# RGB_Ring_SCH.net
KiCad netlist of a schematic drawn in Altium Designer
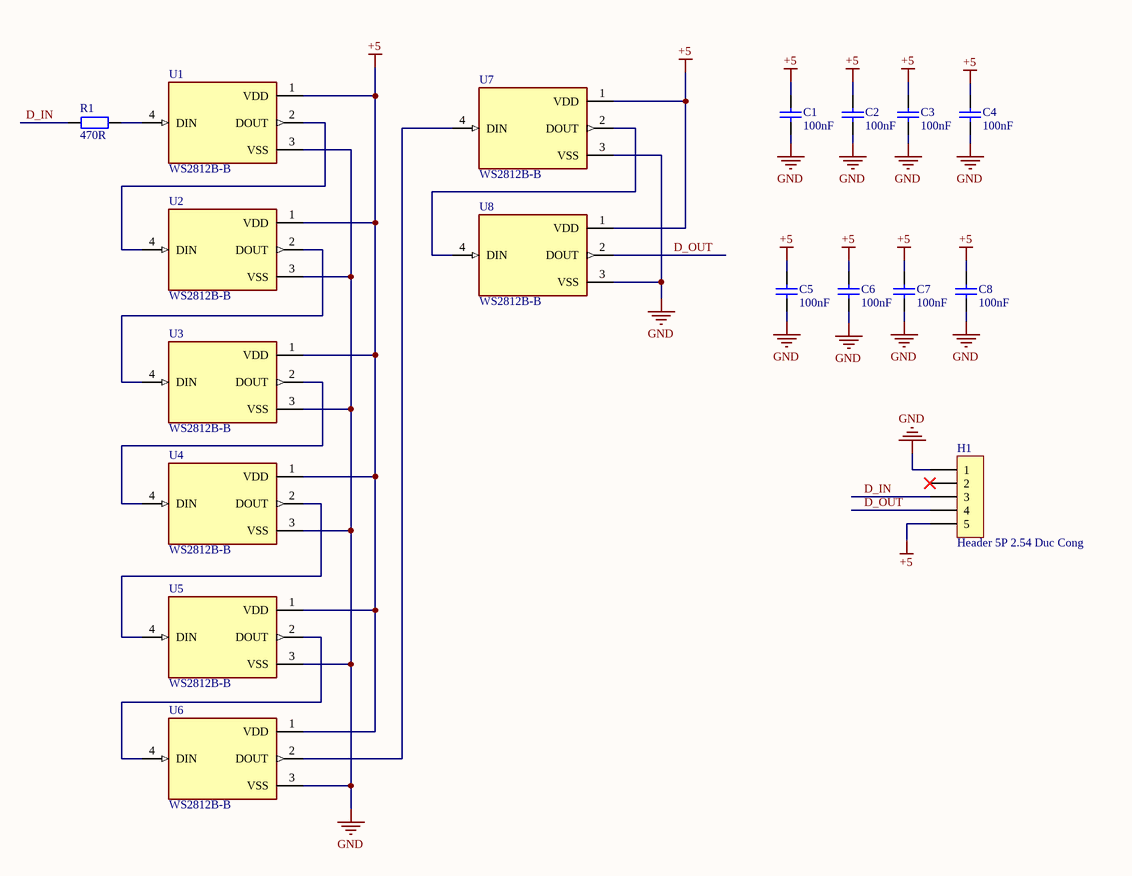
[diagram p0: RGB_Ring_SCH.SchDoc]

(export (version "E")
  (design (tool "Eeschema 10.0.6"))
  (components
    (comp (ref "C1")
      (value "100nF")
      (footprint "tu 0603")
      (description "Dán")
      (libsource (lib "namnt_Lib") (part "Tu 0603 104 50V 10%"))
    )
    (comp (ref "C2")
      (value "100nF")
      (footprint "tu 0603")
      (description "Dán")
      (libsource (lib "namnt_Lib") (part "Tu 0603 104 50V 10%"))
    )
    (comp (ref "C3")
      (value "100nF")
      (footprint "tu 0603")
      (description "Dán")
      (libsource (lib "namnt_Lib") (part "Tu 0603 104 50V 10%"))
    )
    (comp (ref "C4")
      (value "100nF")
      (footprint "tu 0603")
      (description "Dán")
      (libsource (lib "namnt_Lib") (part "Tu 0603 104 50V 10%"))
    )
    (comp (ref "C5")
      (value "100nF")
      (footprint "tu 0603")
      (description "Dán")
      (libsource (lib "namnt_Lib") (part "Tu 0603 104 50V 10%"))
    )
    (comp (ref "C6")
      (value "100nF")
      (footprint "tu 0603")
      (description "Dán")
      (libsource (lib "namnt_Lib") (part "Tu 0603 104 50V 10%"))
    )
    (comp (ref "C7")
      (value "100nF")
      (footprint "tu 0603")
      (description "Dán")
      (libsource (lib "namnt_Lib") (part "Tu 0603 104 50V 10%"))
    )
    (comp (ref "C8")
      (value "100nF")
      (footprint "tu 0603")
      (description "Dán")
      (libsource (lib "namnt_Lib") (part "Tu 0603 104 50V 10%"))
    )
    (comp (ref "H1")
      (value "Header 5P 2.54 Duc Cong")
      (footprint "Header 5P DC 2.54")
      (description "Cắm")
      (libsource (lib "namnt_Lib") (part "Header 5P 2.54 Duc Cong"))
    )
    (comp (ref "R1")
      (value "470R")
      (footprint "tro smd 0603")
      (description "Dán")
      (libsource (lib "namnt_Lib") (part "Tro 0603 5% 470R"))
    )
    (comp (ref "U1")
      (value "WS2812B-B")
      (footprint "LED_WS2812B-B")
      (description "Intelligent control LED integrated light source")
      (libsource (lib "namnt_Lib") (part "WS2812B-B"))
    )
    (comp (ref "U2")
      (value "WS2812B-B")
      (footprint "LED_WS2812B-B")
      (description "Intelligent control LED integrated light source")
      (libsource (lib "namnt_Lib") (part "WS2812B-B"))
    )
    (comp (ref "U3")
      (value "WS2812B-B")
      (footprint "LED_WS2812B-B")
      (description "Intelligent control LED integrated light source")
      (libsource (lib "namnt_Lib") (part "WS2812B-B"))
    )
    (comp (ref "U4")
      (value "WS2812B-B")
      (footprint "LED_WS2812B-B")
      (description "Intelligent control LED integrated light source")
      (libsource (lib "namnt_Lib") (part "WS2812B-B"))
    )
    (comp (ref "U5")
      (value "WS2812B-B")
      (footprint "LED_WS2812B-B")
      (description "Intelligent control LED integrated light source")
      (libsource (lib "namnt_Lib") (part "WS2812B-B"))
    )
    (comp (ref "U6")
      (value "WS2812B-B")
      (footprint "LED_WS2812B-B")
      (description "Intelligent control LED integrated light source")
      (libsource (lib "namnt_Lib") (part "WS2812B-B"))
    )
    (comp (ref "U7")
      (value "WS2812B-B")
      (footprint "LED_WS2812B-B")
      (description "Intelligent control LED integrated light source")
      (libsource (lib "namnt_Lib") (part "WS2812B-B"))
    )
    (comp (ref "U8")
      (value "WS2812B-B")
      (footprint "LED_WS2812B-B")
      (description "Intelligent control LED integrated light source")
      (libsource (lib "namnt_Lib") (part "WS2812B-B"))
    )
  )
  (nets
    (net (code "1") (name "+5") (class "Default")
      (node (ref "C1") (pin "1") (pinfunction "1_1") (pintype "passive"))
      (node (ref "C2") (pin "1") (pinfunction "1_1") (pintype "passive"))
      (node (ref "C3") (pin "1") (pinfunction "1_1") (pintype "passive"))
      (node (ref "C4") (pin "1") (pinfunction "1_1") (pintype "passive"))
      (node (ref "C5") (pin "1") (pinfunction "1_1") (pintype "passive"))
      (node (ref "C6") (pin "1") (pinfunction "1_1") (pintype "passive"))
      (node (ref "C7") (pin "1") (pinfunction "1_1") (pintype "passive"))
      (node (ref "C8") (pin "1") (pinfunction "1_1") (pintype "passive"))
      (node (ref "H1") (pin "5") (pinfunction "5_5") (pintype "passive"))
      (node (ref "U1") (pin "1") (pinfunction "VDD_1") (pintype "power_in"))
      (node (ref "U2") (pin "1") (pinfunction "VDD_1") (pintype "power_in"))
      (node (ref "U3") (pin "1") (pinfunction "VDD_1") (pintype "power_in"))
      (node (ref "U4") (pin "1") (pinfunction "VDD_1") (pintype "power_in"))
      (node (ref "U5") (pin "1") (pinfunction "VDD_1") (pintype "power_in"))
      (node (ref "U6") (pin "1") (pinfunction "VDD_1") (pintype "power_in"))
      (node (ref "U7") (pin "1") (pinfunction "VDD_1") (pintype "power_in"))
      (node (ref "U8") (pin "1") (pinfunction "VDD_1") (pintype "power_in"))
    )
    (net (code "2") (name "/D_IN") (class "Default")
      (node (ref "H1") (pin "3") (pinfunction "3_3") (pintype "passive"))
      (node (ref "R1") (pin "1") (pinfunction "1_1") (pintype "passive"))
    )
    (net (code "3") (name "/D_OUT") (class "Default")
      (node (ref "H1") (pin "4") (pinfunction "4_4") (pintype "passive"))
      (node (ref "U8") (pin "2") (pinfunction "DOUT_2") (pintype "output"))
    )
    (net (code "4") (name "GND") (class "Default")
      (node (ref "C1") (pin "2") (pinfunction "2_2") (pintype "passive"))
      (node (ref "C2") (pin "2") (pinfunction "2_2") (pintype "passive"))
      (node (ref "C3") (pin "2") (pinfunction "2_2") (pintype "passive"))
      (node (ref "C4") (pin "2") (pinfunction "2_2") (pintype "passive"))
      (node (ref "C5") (pin "2") (pinfunction "2_2") (pintype "passive"))
      (node (ref "C6") (pin "2") (pinfunction "2_2") (pintype "passive"))
      (node (ref "C7") (pin "2") (pinfunction "2_2") (pintype "passive"))
      (node (ref "C8") (pin "2") (pinfunction "2_2") (pintype "passive"))
      (node (ref "H1") (pin "1") (pinfunction "1_1") (pintype "passive"))
      (node (ref "U1") (pin "3") (pinfunction "VSS_3") (pintype "power_in"))
      (node (ref "U2") (pin "3") (pinfunction "VSS_3") (pintype "power_in"))
      (node (ref "U3") (pin "3") (pinfunction "VSS_3") (pintype "power_in"))
      (node (ref "U4") (pin "3") (pinfunction "VSS_3") (pintype "power_in"))
      (node (ref "U5") (pin "3") (pinfunction "VSS_3") (pintype "power_in"))
      (node (ref "U6") (pin "3") (pinfunction "VSS_3") (pintype "power_in"))
      (node (ref "U7") (pin "3") (pinfunction "VSS_3") (pintype "power_in"))
      (node (ref "U8") (pin "3") (pinfunction "VSS_3") (pintype "power_in"))
    )
    (net (code "5") (name "Net-(U1-DIN)") (class "Default")
      (node (ref "R1") (pin "2") (pinfunction "2_2") (pintype "passive"))
      (node (ref "U1") (pin "4") (pinfunction "DIN_4") (pintype "input"))
    )
    (net (code "6") (name "Net-(U1-DOUT)") (class "Default")
      (node (ref "U1") (pin "2") (pinfunction "DOUT_2") (pintype "output"))
      (node (ref "U2") (pin "4") (pinfunction "DIN_4") (pintype "input"))
    )
    (net (code "7") (name "Net-(U2-DOUT)") (class "Default")
      (node (ref "U2") (pin "2") (pinfunction "DOUT_2") (pintype "output"))
      (node (ref "U3") (pin "4") (pinfunction "DIN_4") (pintype "input"))
    )
    (net (code "8") (name "Net-(U3-DOUT)") (class "Default")
      (node (ref "U3") (pin "2") (pinfunction "DOUT_2") (pintype "output"))
      (node (ref "U4") (pin "4") (pinfunction "DIN_4") (pintype "input"))
    )
    (net (code "9") (name "Net-(U4-DOUT)") (class "Default")
      (node (ref "U4") (pin "2") (pinfunction "DOUT_2") (pintype "output"))
      (node (ref "U5") (pin "4") (pinfunction "DIN_4") (pintype "input"))
    )
    (net (code "10") (name "Net-(U5-DOUT)") (class "Default")
      (node (ref "U5") (pin "2") (pinfunction "DOUT_2") (pintype "output"))
      (node (ref "U6") (pin "4") (pinfunction "DIN_4") (pintype "input"))
    )
    (net (code "11") (name "Net-(U6-DOUT)") (class "Default")
      (node (ref "U6") (pin "2") (pinfunction "DOUT_2") (pintype "output"))
      (node (ref "U7") (pin "4") (pinfunction "DIN_4") (pintype "input"))
    )
    (net (code "12") (name "Net-(U7-DOUT)") (class "Default")
      (node (ref "U7") (pin "2") (pinfunction "DOUT_2") (pintype "output"))
      (node (ref "U8") (pin "4") (pinfunction "DIN_4") (pintype "input"))
    )
    (net (code "13") (name "unconnected-(H1-Pad2)") (class "Default")
      (node (ref "H1") (pin "2") (pinfunction "2_2") (pintype "passive+no_connect"))
    )
  )
)
